# main_new_layout.net
KiCad netlist of a schematic drawn in EAGLE
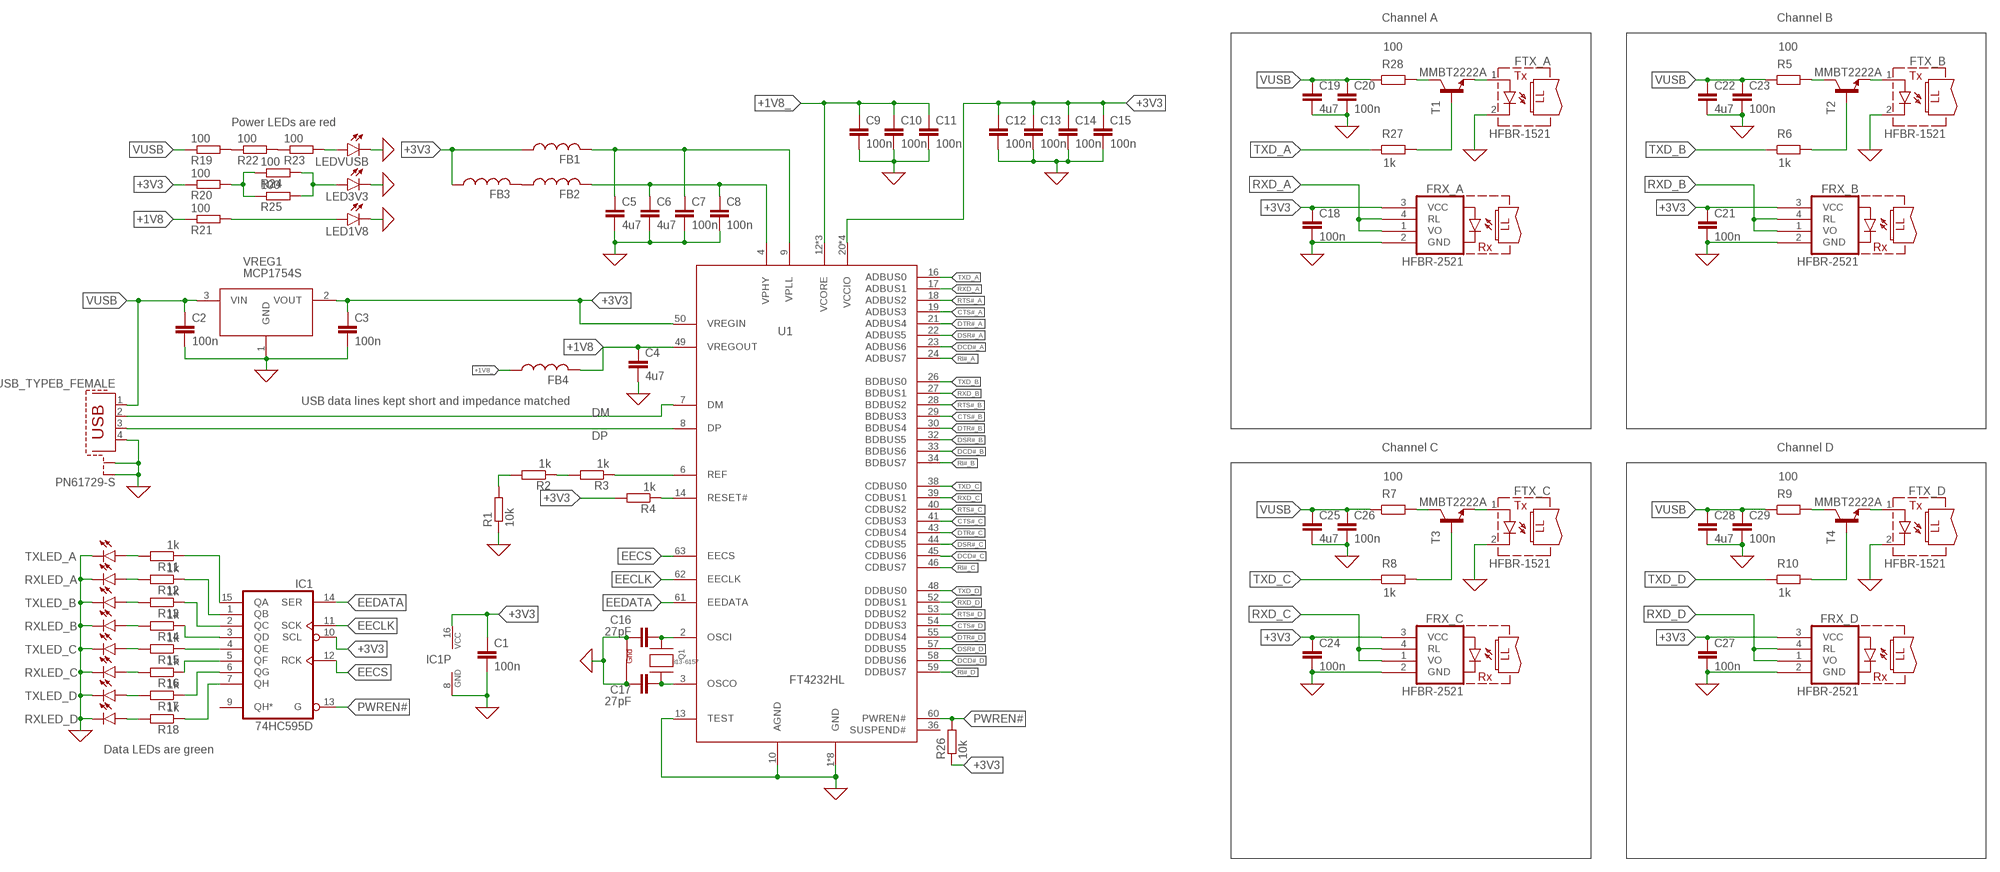
[diagram p0: schematic, sheet 1]

(export (version "E")
  (design (tool "Eeschema 10.0.6"))
  (components
    (comp (ref "C1")
      (value "100n")
      (footprint "eagle-import:C0805")
      (libsource (lib "eagle-import") (part "C-EUC0805"))
    )
    (comp (ref "C2")
      (value "100n")
      (footprint "eagle-import:C0805")
      (libsource (lib "eagle-import") (part "C-EUC0805"))
    )
    (comp (ref "C3")
      (value "100n")
      (footprint "eagle-import:C0805")
      (libsource (lib "eagle-import") (part "C-EUC0805"))
    )
    (comp (ref "C4")
      (value "4u7")
      (footprint "eagle-import:C0805")
      (libsource (lib "eagle-import") (part "C-EUC0805"))
    )
    (comp (ref "C5")
      (value "4u7")
      (footprint "eagle-import:C0805")
      (libsource (lib "eagle-import") (part "C-EUC0805"))
    )
    (comp (ref "C6")
      (value "4u7")
      (footprint "eagle-import:C0805")
      (libsource (lib "eagle-import") (part "C-EUC0805"))
    )
    (comp (ref "C7")
      (value "100n")
      (footprint "eagle-import:C0805")
      (libsource (lib "eagle-import") (part "C-EUC0805"))
    )
    (comp (ref "C8")
      (value "100n")
      (footprint "eagle-import:C0805")
      (libsource (lib "eagle-import") (part "C-EUC0805"))
    )
    (comp (ref "C9")
      (value "100n")
      (footprint "eagle-import:C0805")
      (libsource (lib "eagle-import") (part "C-EUC0805"))
    )
    (comp (ref "C10")
      (value "100n")
      (footprint "eagle-import:C0805")
      (libsource (lib "eagle-import") (part "C-EUC0805"))
    )
    (comp (ref "C11")
      (value "100n")
      (footprint "eagle-import:C0805")
      (libsource (lib "eagle-import") (part "C-EUC0805"))
    )
    (comp (ref "C12")
      (value "100n")
      (footprint "eagle-import:C0805")
      (libsource (lib "eagle-import") (part "C-EUC0805"))
    )
    (comp (ref "C13")
      (value "100n")
      (footprint "eagle-import:C0805")
      (libsource (lib "eagle-import") (part "C-EUC0805"))
    )
    (comp (ref "C14")
      (value "100n")
      (footprint "eagle-import:C0805")
      (libsource (lib "eagle-import") (part "C-EUC0805"))
    )
    (comp (ref "C15")
      (value "100n")
      (footprint "eagle-import:C0805")
      (libsource (lib "eagle-import") (part "C-EUC0805"))
    )
    (comp (ref "C16")
      (value "27pF")
      (footprint "eagle-import:C0805")
      (libsource (lib "eagle-import") (part "C-EUC0805"))
    )
    (comp (ref "C17")
      (value "27pF")
      (footprint "eagle-import:C0805")
      (libsource (lib "eagle-import") (part "C-EUC0805"))
    )
    (comp (ref "C18")
      (value "100n")
      (footprint "eagle-import:C0805")
      (libsource (lib "eagle-import") (part "C-EUC0805"))
    )
    (comp (ref "C19")
      (value "4u7")
      (footprint "eagle-import:C0805")
      (libsource (lib "eagle-import") (part "C-EUC0805"))
    )
    (comp (ref "C20")
      (value "100n")
      (footprint "eagle-import:C0805")
      (libsource (lib "eagle-import") (part "C-EUC0805"))
    )
    (comp (ref "C21")
      (value "100n")
      (footprint "eagle-import:C0805")
      (libsource (lib "eagle-import") (part "C-EUC0805"))
    )
    (comp (ref "C22")
      (value "4u7")
      (footprint "eagle-import:C0805")
      (libsource (lib "eagle-import") (part "C-EUC0805"))
    )
    (comp (ref "C23")
      (value "100n")
      (footprint "eagle-import:C0805")
      (libsource (lib "eagle-import") (part "C-EUC0805"))
    )
    (comp (ref "C24")
      (value "100n")
      (footprint "eagle-import:C0805")
      (libsource (lib "eagle-import") (part "C-EUC0805"))
    )
    (comp (ref "C25")
      (value "4u7")
      (footprint "eagle-import:C0805")
      (libsource (lib "eagle-import") (part "C-EUC0805"))
    )
    (comp (ref "C26")
      (value "100n")
      (footprint "eagle-import:C0805")
      (libsource (lib "eagle-import") (part "C-EUC0805"))
    )
    (comp (ref "C27")
      (value "100n")
      (footprint "eagle-import:C0805")
      (libsource (lib "eagle-import") (part "C-EUC0805"))
    )
    (comp (ref "C28")
      (value "4u7")
      (footprint "eagle-import:C0805")
      (libsource (lib "eagle-import") (part "C-EUC0805"))
    )
    (comp (ref "C29")
      (value "100n")
      (footprint "eagle-import:C0805")
      (libsource (lib "eagle-import") (part "C-EUC0805"))
    )
    (comp (ref "FB1")
      (value "FERRITE")
      (footprint "eagle-import:R0805")
      (libsource (lib "eagle-import") (part "FERRITE"))
    )
    (comp (ref "FB2")
      (value "FERRITE")
      (footprint "eagle-import:R0805")
      (libsource (lib "eagle-import") (part "FERRITE"))
    )
    (comp (ref "FB3")
      (value "FERRITE")
      (footprint "eagle-import:R0805")
      (libsource (lib "eagle-import") (part "FERRITE"))
    )
    (comp (ref "FB4")
      (value "FERRITE")
      (footprint "eagle-import:R0805")
      (libsource (lib "eagle-import") (part "FERRITE"))
    )
    (comp (ref "FRX_A")
      (value "HFBR-2521")
      (footprint "eagle-import:HFBR-15X3")
      (fields (field (name "MF") "AGILENT TECHNOLOGIES"))
      (libsource (lib "eagle-import") (part "HFBR-2521"))
    )
    (comp (ref "FRX_B")
      (value "HFBR-2521")
      (footprint "eagle-import:HFBR-15X3")
      (fields (field (name "MF") "AGILENT TECHNOLOGIES"))
      (libsource (lib "eagle-import") (part "HFBR-2521"))
    )
    (comp (ref "FRX_C")
      (value "HFBR-2521")
      (footprint "eagle-import:HFBR-15X3")
      (fields (field (name "MF") "AGILENT TECHNOLOGIES"))
      (libsource (lib "eagle-import") (part "HFBR-2521"))
    )
    (comp (ref "FRX_D")
      (value "HFBR-2521")
      (footprint "eagle-import:HFBR-15X3")
      (fields (field (name "MF") "AGILENT TECHNOLOGIES"))
      (libsource (lib "eagle-import") (part "HFBR-2521"))
    )
    (comp (ref "FTX_A")
      (value "HFBR-1521")
      (footprint "eagle-import:HFBR-15X3")
      (fields (field (name "MF") "AGILENT TECHNOLOGIES"))
      (libsource (lib "eagle-import") (part "HFBR-1521"))
    )
    (comp (ref "FTX_B")
      (value "HFBR-1521")
      (footprint "eagle-import:HFBR-15X3")
      (fields (field (name "MF") "AGILENT TECHNOLOGIES"))
      (libsource (lib "eagle-import") (part "HFBR-1521"))
    )
    (comp (ref "FTX_C")
      (value "HFBR-1521")
      (footprint "eagle-import:HFBR-15X3")
      (fields (field (name "MF") "AGILENT TECHNOLOGIES"))
      (libsource (lib "eagle-import") (part "HFBR-1521"))
    )
    (comp (ref "FTX_D")
      (value "HFBR-1521")
      (footprint "eagle-import:HFBR-15X3")
      (fields (field (name "MF") "AGILENT TECHNOLOGIES"))
      (libsource (lib "eagle-import") (part "HFBR-1521"))
    )
    (comp (ref "IC1")
      (value "74HC595D")
      (footprint "eagle-import:SO16")
      (libsource (lib "eagle-import") (part "74595DHC"))
    )
    (comp (ref "LED1V8")
      (value "LEDCHIP-LED0805")
      (footprint "eagle-import:CHIP-LED0805")
      (libsource (lib "eagle-import") (part "LEDCHIP-LED0805"))
    )
    (comp (ref "LED3V3")
      (value "LEDCHIP-LED0805")
      (footprint "eagle-import:CHIP-LED0805")
      (libsource (lib "eagle-import") (part "LEDCHIP-LED0805"))
    )
    (comp (ref "LEDVUSB")
      (value "LEDCHIP-LED0805")
      (footprint "eagle-import:CHIP-LED0805")
      (libsource (lib "eagle-import") (part "LEDCHIP-LED0805"))
    )
    (comp (ref "Q1")
      (value "XTAL-4-3225")
      (footprint "eagle-import:NX3225")
      (libsource (lib "eagle-import") (part "XTAL-4-3225"))
    )
    (comp (ref "R1")
      (value "10k")
      (footprint "eagle-import:R0805")
      (libsource (lib "eagle-import") (part "R-EU_R0805"))
    )
    (comp (ref "R2")
      (value "1k")
      (footprint "eagle-import:R0805")
      (libsource (lib "eagle-import") (part "R-EU_R0805"))
    )
    (comp (ref "R3")
      (value "1k")
      (footprint "eagle-import:R0805")
      (libsource (lib "eagle-import") (part "R-EU_R0805"))
    )
    (comp (ref "R4")
      (value "1k")
      (footprint "eagle-import:R0805")
      (libsource (lib "eagle-import") (part "R-EU_R0805"))
    )
    (comp (ref "R5")
      (value "100")
      (footprint "eagle-import:R0805")
      (fields (field (name "SPICEPREFIX") "R"))
      (libsource (lib "eagle-import") (part "R-EU_R0805"))
    )
    (comp (ref "R6")
      (value "1k")
      (footprint "eagle-import:R0805")
      (libsource (lib "eagle-import") (part "R-EU_R0805"))
    )
    (comp (ref "R7")
      (value "100")
      (footprint "eagle-import:R0805")
      (fields (field (name "SPICEPREFIX") "R"))
      (libsource (lib "eagle-import") (part "R-EU_R0805"))
    )
    (comp (ref "R8")
      (value "1k")
      (footprint "eagle-import:R0805")
      (libsource (lib "eagle-import") (part "R-EU_R0805"))
    )
    (comp (ref "R9")
      (value "100")
      (footprint "eagle-import:R0805")
      (fields (field (name "SPICEPREFIX") "R"))
      (libsource (lib "eagle-import") (part "R-EU_R0805"))
    )
    (comp (ref "R10")
      (value "1k")
      (footprint "eagle-import:R0805")
      (libsource (lib "eagle-import") (part "R-EU_R0805"))
    )
    (comp (ref "R11")
      (value "1k")
      (footprint "eagle-import:R0805")
      (libsource (lib "eagle-import") (part "R-EU_R0805"))
    )
    (comp (ref "R12")
      (value "1k")
      (footprint "eagle-import:R0805")
      (libsource (lib "eagle-import") (part "R-EU_R0805"))
    )
    (comp (ref "R13")
      (value "1k")
      (footprint "eagle-import:R0805")
      (libsource (lib "eagle-import") (part "R-EU_R0805"))
    )
    (comp (ref "R14")
      (value "1k")
      (footprint "eagle-import:R0805")
      (libsource (lib "eagle-import") (part "R-EU_R0805"))
    )
    (comp (ref "R15")
      (value "1k")
      (footprint "eagle-import:R0805")
      (libsource (lib "eagle-import") (part "R-EU_R0805"))
    )
    (comp (ref "R16")
      (value "1k")
      (footprint "eagle-import:R0805")
      (libsource (lib "eagle-import") (part "R-EU_R0805"))
    )
    (comp (ref "R17")
      (value "1k")
      (footprint "eagle-import:R0805")
      (libsource (lib "eagle-import") (part "R-EU_R0805"))
    )
    (comp (ref "R18")
      (value "1k")
      (footprint "eagle-import:R0805")
      (libsource (lib "eagle-import") (part "R-EU_R0805"))
    )
    (comp (ref "R19")
      (value "100")
      (footprint "eagle-import:R0805")
      (libsource (lib "eagle-import") (part "R-EU_R0805"))
    )
    (comp (ref "R20")
      (value "100")
      (footprint "eagle-import:R0805")
      (libsource (lib "eagle-import") (part "R-EU_R0805"))
    )
    (comp (ref "R21")
      (value "100")
      (footprint "eagle-import:R0805")
      (libsource (lib "eagle-import") (part "R-EU_R0805"))
    )
    (comp (ref "R22")
      (value "100")
      (footprint "eagle-import:R0805")
      (libsource (lib "eagle-import") (part "R-EU_R0805"))
    )
    (comp (ref "R23")
      (value "100")
      (footprint "eagle-import:R0805")
      (libsource (lib "eagle-import") (part "R-EU_R0805"))
    )
    (comp (ref "R24")
      (value "100")
      (footprint "eagle-import:R0805")
      (libsource (lib "eagle-import") (part "R-EU_R0805"))
    )
    (comp (ref "R25")
      (value "100")
      (footprint "eagle-import:R0805")
      (libsource (lib "eagle-import") (part "R-EU_R0805"))
    )
    (comp (ref "R26")
      (value "10k")
      (footprint "eagle-import:R0805")
      (libsource (lib "eagle-import") (part "R-EU_R0805"))
    )
    (comp (ref "R27")
      (value "1k")
      (footprint "eagle-import:R0805")
      (libsource (lib "eagle-import") (part "R-EU_R0805"))
    )
    (comp (ref "R28")
      (value "100")
      (footprint "eagle-import:R0805")
      (fields (field (name "SPICEPREFIX") "R"))
      (libsource (lib "eagle-import") (part "R-EU_R0805"))
    )
    (comp (ref "RXLED_A")
      (value "LEDCHIP-LED0805")
      (footprint "eagle-import:CHIP-LED0805")
      (libsource (lib "eagle-import") (part "LEDCHIP-LED0805"))
    )
    (comp (ref "RXLED_B")
      (value "LEDCHIP-LED0805")
      (footprint "eagle-import:CHIP-LED0805")
      (libsource (lib "eagle-import") (part "LEDCHIP-LED0805"))
    )
    (comp (ref "RXLED_C")
      (value "LEDCHIP-LED0805")
      (footprint "eagle-import:CHIP-LED0805")
      (libsource (lib "eagle-import") (part "LEDCHIP-LED0805"))
    )
    (comp (ref "RXLED_D")
      (value "LEDCHIP-LED0805")
      (footprint "eagle-import:CHIP-LED0805")
      (libsource (lib "eagle-import") (part "LEDCHIP-LED0805"))
    )
    (comp (ref "T1")
      (value "MMBT2222A")
      (footprint "eagle-import:SOT23-BEC")
      (libsource (lib "eagle-import") (part "-NPN-SOT23-BECBC847A"))
    )
    (comp (ref "T2")
      (value "MMBT2222A")
      (footprint "eagle-import:SOT23-BEC")
      (libsource (lib "eagle-import") (part "-NPN-SOT23-BECBC847A"))
    )
    (comp (ref "T3")
      (value "MMBT2222A")
      (footprint "eagle-import:SOT23-BEC")
      (libsource (lib "eagle-import") (part "-NPN-SOT23-BECBC847A"))
    )
    (comp (ref "T4")
      (value "MMBT2222A")
      (footprint "eagle-import:SOT23-BEC")
      (libsource (lib "eagle-import") (part "-NPN-SOT23-BECBC847A"))
    )
    (comp (ref "TXLED_A")
      (value "LEDCHIP-LED0805")
      (footprint "eagle-import:CHIP-LED0805")
      (libsource (lib "eagle-import") (part "LEDCHIP-LED0805"))
    )
    (comp (ref "TXLED_B")
      (value "LEDCHIP-LED0805")
      (footprint "eagle-import:CHIP-LED0805")
      (libsource (lib "eagle-import") (part "LEDCHIP-LED0805"))
    )
    (comp (ref "TXLED_C")
      (value "LEDCHIP-LED0805")
      (footprint "eagle-import:CHIP-LED0805")
      (libsource (lib "eagle-import") (part "LEDCHIP-LED0805"))
    )
    (comp (ref "TXLED_D")
      (value "LEDCHIP-LED0805")
      (footprint "eagle-import:CHIP-LED0805")
      (libsource (lib "eagle-import") (part "LEDCHIP-LED0805"))
    )
    (comp (ref "U1")
      (value "FT4232HL")
      (footprint "eagle-import:LQFP-ST-64-2")
      (libsource (lib "eagle-import") (part "FT4232HL"))
    )
    (comp (ref "USB_TYPEB_FEMALE")
      (value "PN61729-S")
      (footprint "eagle-import:PN61729-S")
      (libsource (lib "eagle-import") (part "PN61729-S"))
    )
    (comp (ref "VREG1")
      (value "MCP1754S")
      (footprint "eagle-import:SOT23")
      (libsource (lib "eagle-import") (part "MCP1754S"))
    )
  )
  (nets
    (net (code "1") (name "+1V8") (class "Default")
      (node (ref "C4") (pin "1") (pinfunction "1_1") (pintype "passive"))
      (node (ref "FB4") (pin "2") (pinfunction "2_2") (pintype "passive"))
      (node (ref "R21") (pin "1") (pinfunction "1_1") (pintype "passive"))
      (node (ref "U1") (pin "49") (pinfunction "VREGOUT_49") (pintype "bidirectional"))
    )
    (net (code "2") (name "+1V8_") (class "Default")
      (node (ref "C10") (pin "1") (pinfunction "1_1") (pintype "passive"))
      (node (ref "C11") (pin "1") (pinfunction "1_1") (pintype "passive"))
      (node (ref "C9") (pin "1") (pinfunction "1_1") (pintype "passive"))
      (node (ref "FB4") (pin "1") (pinfunction "1_1") (pintype "passive"))
      (node (ref "U1") (pin "12") (pinfunction "VCORE_12") (pintype "bidirectional"))
      (node (ref "U1") (pin "37") (pinfunction "VCORE_37") (pintype "bidirectional"))
      (node (ref "U1") (pin "64") (pinfunction "VCORE_64") (pintype "bidirectional"))
    )
    (net (code "3") (name "+3V3") (class "Default")
      (node (ref "C1") (pin "1") (pinfunction "1_1") (pintype "passive"))
      (node (ref "C12") (pin "1") (pinfunction "1_1") (pintype "passive"))
      (node (ref "C13") (pin "1") (pinfunction "1_1") (pintype "passive"))
      (node (ref "C14") (pin "1") (pinfunction "1_1") (pintype "passive"))
      (node (ref "C15") (pin "1") (pinfunction "1_1") (pintype "passive"))
      (node (ref "C18") (pin "1") (pinfunction "1_1") (pintype "passive"))
      (node (ref "C21") (pin "1") (pinfunction "1_1") (pintype "passive"))
      (node (ref "C24") (pin "1") (pinfunction "1_1") (pintype "passive"))
      (node (ref "C27") (pin "1") (pinfunction "1_1") (pintype "passive"))
      (node (ref "C3") (pin "1") (pinfunction "1_1") (pintype "passive"))
      (node (ref "FB1") (pin "1") (pinfunction "1_1") (pintype "passive"))
      (node (ref "FB3") (pin "1") (pinfunction "1_1") (pintype "passive"))
      (node (ref "FRX_A") (pin "3") (pinfunction "VCC_3") (pintype "power_in"))
      (node (ref "FRX_B") (pin "3") (pinfunction "VCC_3") (pintype "power_in"))
      (node (ref "FRX_C") (pin "3") (pinfunction "VCC_3") (pintype "power_in"))
      (node (ref "FRX_D") (pin "3") (pinfunction "VCC_3") (pintype "power_in"))
      (node (ref "IC1") (pin "10") (pinfunction "SCL_10") (pintype "input"))
      (node (ref "IC1") (pin "16") (pinfunction "VCC_16") (pintype "power_in"))
      (node (ref "R20") (pin "1") (pinfunction "1_1") (pintype "passive"))
      (node (ref "R26") (pin "1") (pinfunction "1_1") (pintype "passive"))
      (node (ref "R4") (pin "2") (pinfunction "2_2") (pintype "passive"))
      (node (ref "U1") (pin "20") (pinfunction "VCCIO_20") (pintype "bidirectional"))
      (node (ref "U1") (pin "31") (pinfunction "VCCIO_31") (pintype "bidirectional"))
      (node (ref "U1") (pin "42") (pinfunction "VCCIO_42") (pintype "bidirectional"))
      (node (ref "U1") (pin "50") (pinfunction "VREGIN_50") (pintype "bidirectional"))
      (node (ref "U1") (pin "56") (pinfunction "VCCIO_56") (pintype "bidirectional"))
      (node (ref "VREG1") (pin "2") (pinfunction "VOUT_2") (pintype "bidirectional"))
    )
    (net (code "4") (name "/DM") (class "Default")
      (node (ref "U1") (pin "7") (pinfunction "DM_7") (pintype "bidirectional"))
      (node (ref "USB_TYPEB_FEMALE") (pin "2") (pinfunction "2_2") (pintype "passive"))
    )
    (net (code "5") (name "/DP") (class "Default")
      (node (ref "U1") (pin "8") (pinfunction "DP_8") (pintype "bidirectional"))
      (node (ref "USB_TYPEB_FEMALE") (pin "3") (pinfunction "3_3") (pintype "passive"))
    )
    (net (code "6") (name "CTS#_A") (class "Default")
      (node (ref "U1") (pin "19") (pinfunction "ADBUS3_19") (pintype "bidirectional"))
    )
    (net (code "7") (name "CTS#_B") (class "Default")
      (node (ref "U1") (pin "29") (pinfunction "BDBUS3_29") (pintype "bidirectional"))
    )
    (net (code "8") (name "CTS#_C") (class "Default")
      (node (ref "U1") (pin "41") (pinfunction "CDBUS3_41") (pintype "bidirectional"))
    )
    (net (code "9") (name "CTS#_D") (class "Default")
      (node (ref "U1") (pin "54") (pinfunction "DDBUS3_54") (pintype "bidirectional"))
    )
    (net (code "10") (name "DCD#_A") (class "Default")
      (node (ref "U1") (pin "23") (pinfunction "ADBUS6_23") (pintype "bidirectional"))
    )
    (net (code "11") (name "DCD#_B") (class "Default")
      (node (ref "U1") (pin "33") (pinfunction "BDBUS6_33") (pintype "bidirectional"))
    )
    (net (code "12") (name "DCD#_C") (class "Default")
      (node (ref "U1") (pin "45") (pinfunction "CDBUS6_45") (pintype "bidirectional"))
    )
    (net (code "13") (name "DCD#_D") (class "Default")
      (node (ref "U1") (pin "58") (pinfunction "DDBUS6_58") (pintype "bidirectional"))
    )
    (net (code "14") (name "DSR#_A") (class "Default")
      (node (ref "U1") (pin "22") (pinfunction "ADBUS5_22") (pintype "bidirectional"))
    )
    (net (code "15") (name "DSR#_B") (class "Default")
      (node (ref "U1") (pin "32") (pinfunction "BDBUS5_32") (pintype "bidirectional"))
    )
    (net (code "16") (name "DSR#_C") (class "Default")
      (node (ref "U1") (pin "44") (pinfunction "CDBUS5_44") (pintype "bidirectional"))
    )
    (net (code "17") (name "DSR#_D") (class "Default")
      (node (ref "U1") (pin "57") (pinfunction "DDBUS5_57") (pintype "bidirectional"))
    )
    (net (code "18") (name "DTR#_A") (class "Default")
      (node (ref "U1") (pin "21") (pinfunction "ADBUS4_21") (pintype "bidirectional"))
    )
    (net (code "19") (name "DTR#_B") (class "Default")
      (node (ref "U1") (pin "30") (pinfunction "BDBUS4_30") (pintype "bidirectional"))
    )
    (net (code "20") (name "DTR#_C") (class "Default")
      (node (ref "U1") (pin "43") (pinfunction "CDBUS4_43") (pintype "bidirectional"))
    )
    (net (code "21") (name "DTR#_D") (class "Default")
      (node (ref "U1") (pin "55") (pinfunction "DDBUS4_55") (pintype "bidirectional"))
    )
    (net (code "22") (name "EECLK") (class "Default")
      (node (ref "IC1") (pin "11") (pinfunction "SCK_11") (pintype "input"))
      (node (ref "U1") (pin "62") (pinfunction "EECLK_62") (pintype "bidirectional"))
    )
    (net (code "23") (name "EECS") (class "Default")
      (node (ref "IC1") (pin "12") (pinfunction "RCK_12") (pintype "input"))
      (node (ref "U1") (pin "63") (pinfunction "EECS_63") (pintype "bidirectional"))
    )
    (net (code "24") (name "EEDATA") (class "Default")
      (node (ref "IC1") (pin "14") (pinfunction "SER_14") (pintype "input"))
      (node (ref "U1") (pin "61") (pinfunction "EEDATA_61") (pintype "bidirectional"))
    )
    (net (code "25") (name "GND") (class "Default")
      (node (ref "C1") (pin "2") (pinfunction "2_2") (pintype "passive"))
      (node (ref "C10") (pin "2") (pinfunction "2_2") (pintype "passive"))
      (node (ref "C11") (pin "2") (pinfunction "2_2") (pintype "passive"))
      (node (ref "C12") (pin "2") (pinfunction "2_2") (pintype "passive"))
      (node (ref "C13") (pin "2") (pinfunction "2_2") (pintype "passive"))
      (node (ref "C14") (pin "2") (pinfunction "2_2") (pintype "passive"))
      (node (ref "C15") (pin "2") (pinfunction "2_2") (pintype "passive"))
      (node (ref "C16") (pin "2") (pinfunction "2_2") (pintype "passive"))
      (node (ref "C17") (pin "2") (pinfunction "2_2") (pintype "passive"))
      (node (ref "C18") (pin "2") (pinfunction "2_2") (pintype "passive"))
      (node (ref "C19") (pin "2") (pinfunction "2_2") (pintype "passive"))
      (node (ref "C2") (pin "2") (pinfunction "2_2") (pintype "passive"))
      (node (ref "C20") (pin "2") (pinfunction "2_2") (pintype "passive"))
      (node (ref "C21") (pin "2") (pinfunction "2_2") (pintype "passive"))
      (node (ref "C22") (pin "2") (pinfunction "2_2") (pintype "passive"))
      (node (ref "C23") (pin "2") (pinfunction "2_2") (pintype "passive"))
      (node (ref "C24") (pin "2") (pinfunction "2_2") (pintype "passive"))
      (node (ref "C25") (pin "2") (pinfunction "2_2") (pintype "passive"))
      (node (ref "C26") (pin "2") (pinfunction "2_2") (pintype "passive"))
      (node (ref "C27") (pin "2") (pinfunction "2_2") (pintype "passive"))
      (node (ref "C28") (pin "2") (pinfunction "2_2") (pintype "passive"))
      (node (ref "C29") (pin "2") (pinfunction "2_2") (pintype "passive"))
      (node (ref "C3") (pin "2") (pinfunction "2_2") (pintype "passive"))
      (node (ref "C4") (pin "2") (pinfunction "2_2") (pintype "passive"))
      (node (ref "C5") (pin "2") (pinfunction "2_2") (pintype "passive"))
      (node (ref "C6") (pin "2") (pinfunction "2_2") (pintype "passive"))
      (node (ref "C7") (pin "2") (pinfunction "2_2") (pintype "passive"))
      (node (ref "C8") (pin "2") (pinfunction "2_2") (pintype "passive"))
      (node (ref "C9") (pin "2") (pinfunction "2_2") (pintype "passive"))
      (node (ref "FRX_A") (pin "2") (pinfunction "GND_2") (pintype "power_in"))
      (node (ref "FRX_B") (pin "2") (pinfunction "GND_2") (pintype "power_in"))
      (node (ref "FRX_C") (pin "2") (pinfunction "GND_2") (pintype "power_in"))
      (node (ref "FRX_D") (pin "2") (pinfunction "GND_2") (pintype "power_in"))
      (node (ref "FTX_A") (pin "2") (pinfunction "C_2") (pintype "passive"))
      (node (ref "FTX_B") (pin "2") (pinfunction "C_2") (pintype "passive"))
      (node (ref "FTX_C") (pin "2") (pinfunction "C_2") (pintype "passive"))
      (node (ref "FTX_D") (pin "2") (pinfunction "C_2") (pintype "passive"))
      (node (ref "IC1") (pin "8") (pinfunction "GND_8") (pintype "power_in"))
      (node (ref "LED1V8") (pin "C") (pinfunction "C_C") (pintype "passive"))
      (node (ref "LED3V3") (pin "C") (pinfunction "C_C") (pintype "passive"))
      (node (ref "LEDVUSB") (pin "C") (pinfunction "C_C") (pintype "passive"))
      (node (ref "Q1") (pin "2") (pinfunction "G2_2") (pintype "power_in"))
      (node (ref "Q1") (pin "4") (pinfunction "G1_4") (pintype "power_in"))
      (node (ref "R1") (pin "1") (pinfunction "1_1") (pintype "passive"))
      (node (ref "RXLED_A") (pin "C") (pinfunction "C_C") (pintype "passive"))
      (node (ref "RXLED_B") (pin "C") (pinfunction "C_C") (pintype "passive"))
      (node (ref "RXLED_C") (pin "C") (pinfunction "C_C") (pintype "passive"))
      (node (ref "RXLED_D") (pin "C") (pinfunction "C_C") (pintype "passive"))
      (node (ref "TXLED_A") (pin "C") (pinfunction "C_C") (pintype "passive"))
      (node (ref "TXLED_B") (pin "C") (pinfunction "C_C") (pintype "passive"))
      (node (ref "TXLED_C") (pin "C") (pinfunction "C_C") (pintype "passive"))
      (node (ref "TXLED_D") (pin "C") (pinfunction "C_C") (pintype "passive"))
      (node (ref "U1") (pin "1") (pinfunction "GND_1") (pintype "bidirectional"))
      (node (ref "U1") (pin "10") (pinfunction "AGND_10") (pintype "bidirectional"))
      (node (ref "U1") (pin "11") (pinfunction "GND_11") (pintype "bidirectional"))
      (node (ref "U1") (pin "13") (pinfunction "TEST_13") (pintype "bidirectional"))
      (node (ref "U1") (pin "15") (pinfunction "GND_15") (pintype "bidirectional"))
      (node (ref "U1") (pin "25") (pinfunction "GND_25") (pintype "bidirectional"))
      (node (ref "U1") (pin "35") (pinfunction "GND_35") (pintype "bidirectional"))
      (node (ref "U1") (pin "47") (pinfunction "GND_47") (pintype "bidirectional"))
      (node (ref "U1") (pin "5") (pinfunction "GND_5") (pintype "bidirectional"))
      (node (ref "U1") (pin "51") (pinfunction "GND_51") (pintype "bidirectional"))
      (node (ref "USB_TYPEB_FEMALE") (pin "4") (pinfunction "4_4") (pintype "passive"))
      (node (ref "USB_TYPEB_FEMALE") (pin "S1") (pinfunction "S1_S1") (pintype "passive"))
      (node (ref "USB_TYPEB_FEMALE") (pin "S2") (pinfunction "S2_S2") (pintype "passive"))
      (node (ref "VREG1") (pin "1") (pinfunction "GND_1") (pintype "bidirectional"))
    )
    (net (code "26") (name "Net-(FB2-Pad1)") (class "Default")
      (node (ref "FB2") (pin "1") (pinfunction "1_1") (pintype "passive"))
      (node (ref "FB3") (pin "2") (pinfunction "2_2") (pintype "passive"))
    )
    (net (code "27") (name "Net-(FTX_A-A)") (class "Default")
      (node (ref "FTX_A") (pin "1") (pinfunction "A_1") (pintype "passive"))
      (node (ref "T1") (pin "E") (pinfunction "E_E") (pintype "passive"))
    )
    (net (code "28") (name "Net-(FTX_B-A)") (class "Default")
      (node (ref "FTX_B") (pin "1") (pinfunction "A_1") (pintype "passive"))
      (node (ref "T2") (pin "E") (pinfunction "E_E") (pintype "passive"))
    )
    (net (code "29") (name "Net-(FTX_C-A)") (class "Default")
      (node (ref "FTX_C") (pin "1") (pinfunction "A_1") (pintype "passive"))
      (node (ref "T3") (pin "E") (pinfunction "E_E") (pintype "passive"))
    )
    (net (code "30") (name "Net-(FTX_D-A)") (class "Default")
      (node (ref "FTX_D") (pin "1") (pinfunction "A_1") (pintype "passive"))
      (node (ref "T4") (pin "E") (pinfunction "E_E") (pintype "passive"))
    )
    (net (code "31") (name "Net-(IC1A-QA)") (class "Default")
      (node (ref "IC1") (pin "15") (pinfunction "QA_15") (pintype "tri_state"))
      (node (ref "R11") (pin "1") (pinfunction "1_1") (pintype "passive"))
    )
    (net (code "32") (name "Net-(IC1A-QB)") (class "Default")
      (node (ref "IC1") (pin "1") (pinfunction "QB_1") (pintype "tri_state"))
      (node (ref "R12") (pin "1") (pinfunction "1_1") (pintype "passive"))
    )
    (net (code "33") (name "Net-(IC1A-QC)") (class "Default")
      (node (ref "IC1") (pin "2") (pinfunction "QC_2") (pintype "tri_state"))
      (node (ref "R13") (pin "1") (pinfunction "1_1") (pintype "passive"))
    )
    (net (code "34") (name "Net-(IC1A-QD)") (class "Default")
      (node (ref "IC1") (pin "3") (pinfunction "QD_3") (pintype "tri_state"))
      (node (ref "R14") (pin "1") (pinfunction "1_1") (pintype "passive"))
    )
    (net (code "35") (name "Net-(IC1A-QE)") (class "Default")
      (node (ref "IC1") (pin "4") (pinfunction "QE_4") (pintype "tri_state"))
      (node (ref "R15") (pin "1") (pinfunction "1_1") (pintype "passive"))
    )
    (net (code "36") (name "Net-(IC1A-QF)") (class "Default")
      (node (ref "IC1") (pin "5") (pinfunction "QF_5") (pintype "tri_state"))
      (node (ref "R16") (pin "1") (pinfunction "1_1") (pintype "passive"))
    )
    (net (code "37") (name "Net-(IC1A-QG)") (class "Default")
      (node (ref "IC1") (pin "6") (pinfunction "QG_6") (pintype "tri_state"))
      (node (ref "R17") (pin "1") (pinfunction "1_1") (pintype "passive"))
    )
    (net (code "38") (name "Net-(IC1A-QH)") (class "Default")
      (node (ref "IC1") (pin "7") (pinfunction "QH_7") (pintype "tri_state"))
      (node (ref "R18") (pin "1") (pinfunction "1_1") (pintype "passive"))
    )
    (net (code "39") (name "Net-(LED1V8-PadA)") (class "Default")
      (node (ref "LED1V8") (pin "A") (pinfunction "A_A") (pintype "passive"))
      (node (ref "R21") (pin "2") (pinfunction "2_2") (pintype "passive"))
    )
    (net (code "40") (name "Net-(LED3V3-PadA)") (class "Default")
      (node (ref "LED3V3") (pin "A") (pinfunction "A_A") (pintype "passive"))
      (node (ref "R24") (pin "2") (pinfunction "2_2") (pintype "passive"))
      (node (ref "R25") (pin "2") (pinfunction "2_2") (pintype "passive"))
    )
    (net (code "41") (name "Net-(LEDVUSB-PadA)") (class "Default")
      (node (ref "LEDVUSB") (pin "A") (pinfunction "A_A") (pintype "passive"))
      (node (ref "R23") (pin "2") (pinfunction "2_2") (pintype "passive"))
    )
    (net (code "42") (name "Net-(Q1-X1)") (class "Default")
      (node (ref "C16") (pin "1") (pinfunction "1_1") (pintype "passive"))
      (node (ref "Q1") (pin "1") (pinfunction "X1_1") (pintype "bidirectional"))
      (node (ref "U1") (pin "2") (pinfunction "OSCI_2") (pintype "bidirectional"))
    )
    (net (code "43") (name "Net-(Q1-X2)") (class "Default")
      (node (ref "C17") (pin "1") (pinfunction "1_1") (pintype "passive"))
      (node (ref "Q1") (pin "3") (pinfunction "X2_3") (pintype "bidirectional"))
      (node (ref "U1") (pin "3") (pinfunction "OSCO_3") (pintype "bidirectional"))
    )
    (net (code "44") (name "Net-(R1-Pad2)") (class "Default")
      (node (ref "R1") (pin "2") (pinfunction "2_2") (pintype "passive"))
      (node (ref "R2") (pin "2") (pinfunction "2_2") (pintype "passive"))
    )
    (net (code "45") (name "Net-(R2-Pad1)") (class "Default")
      (node (ref "R2") (pin "1") (pinfunction "1_1") (pintype "passive"))
      (node (ref "R3") (pin "2") (pinfunction "2_2") (pintype "passive"))
    )
    (net (code "46") (name "Net-(R5-Pad2)") (class "Default")
      (node (ref "R5") (pin "2") (pinfunction "2_2") (pintype "passive"))
      (node (ref "T2") (pin "C") (pinfunction "C_C") (pintype "passive"))
    )
    (net (code "47") (name "Net-(R6-Pad2)") (class "Default")
      (node (ref "R6") (pin "2") (pinfunction "2_2") (pintype "passive"))
      (node (ref "T2") (pin "B") (pinfunction "B_B") (pintype "passive"))
    )
    (net (code "48") (name "Net-(R7-Pad2)") (class "Default")
      (node (ref "R7") (pin "2") (pinfunction "2_2") (pintype "passive"))
      (node (ref "T3") (pin "C") (pinfunction "C_C") (pintype "passive"))
    )
    (net (code "49") (name "Net-(R8-Pad2)") (class "Default")
      (node (ref "R8") (pin "2") (pinfunction "2_2") (pintype "passive"))
      (node (ref "T3") (pin "B") (pinfunction "B_B") (pintype "passive"))
    )
    (net (code "50") (name "Net-(R9-Pad2)") (class "Default")
      (node (ref "R9") (pin "2") (pinfunction "2_2") (pintype "passive"))
      (node (ref "T4") (pin "C") (pinfunction "C_C") (pintype "passive"))
    )
    (net (code "51") (name "Net-(R10-Pad2)") (class "Default")
      (node (ref "R10") (pin "2") (pinfunction "2_2") (pintype "passive"))
      (node (ref "T4") (pin "B") (pinfunction "B_B") (pintype "passive"))
    )
    (net (code "52") (name "Net-(R11-Pad2)") (class "Default")
      (node (ref "R11") (pin "2") (pinfunction "2_2") (pintype "passive"))
      (node (ref "TXLED_A") (pin "A") (pinfunction "A_A") (pintype "passive"))
    )
    (net (code "53") (name "Net-(R12-Pad2)") (class "Default")
      (node (ref "R12") (pin "2") (pinfunction "2_2") (pintype "passive"))
      (node (ref "RXLED_A") (pin "A") (pinfunction "A_A") (pintype "passive"))
    )
    (net (code "54") (name "Net-(R13-Pad2)") (class "Default")
      (node (ref "R13") (pin "2") (pinfunction "2_2") (pintype "passive"))
      (node (ref "TXLED_B") (pin "A") (pinfunction "A_A") (pintype "passive"))
    )
    (net (code "55") (name "Net-(R14-Pad2)") (class "Default")
      (node (ref "R14") (pin "2") (pinfunction "2_2") (pintype "passive"))
      (node (ref "RXLED_B") (pin "A") (pinfunction "A_A") (pintype "passive"))
    )
    (net (code "56") (name "Net-(R15-Pad2)") (class "Default")
      (node (ref "R15") (pin "2") (pinfunction "2_2") (pintype "passive"))
      (node (ref "TXLED_C") (pin "A") (pinfunction "A_A") (pintype "passive"))
    )
    (net (code "57") (name "Net-(R16-Pad2)") (class "Default")
      (node (ref "R16") (pin "2") (pinfunction "2_2") (pintype "passive"))
      (node (ref "RXLED_C") (pin "A") (pinfunction "A_A") (pintype "passive"))
    )
    (net (code "58") (name "Net-(R17-Pad2)") (class "Default")
      (node (ref "R17") (pin "2") (pinfunction "2_2") (pintype "passive"))
      (node (ref "TXLED_D") (pin "A") (pinfunction "A_A") (pintype "passive"))
    )
    (net (code "59") (name "Net-(R18-Pad2)") (class "Default")
      (node (ref "R18") (pin "2") (pinfunction "2_2") (pintype "passive"))
      (node (ref "RXLED_D") (pin "A") (pinfunction "A_A") (pintype "passive"))
    )
    (net (code "60") (name "Net-(R19-Pad2)") (class "Default")
      (node (ref "R19") (pin "2") (pinfunction "2_2") (pintype "passive"))
      (node (ref "R22") (pin "1") (pinfunction "1_1") (pintype "passive"))
    )
    (net (code "61") (name "Net-(R20-Pad2)") (class "Default")
      (node (ref "R20") (pin "2") (pinfunction "2_2") (pintype "passive"))
      (node (ref "R24") (pin "1") (pinfunction "1_1") (pintype "passive"))
      (node (ref "R25") (pin "1") (pinfunction "1_1") (pintype "passive"))
    )
    (net (code "62") (name "Net-(R22-Pad2)") (class "Default")
      (node (ref "R22") (pin "2") (pinfunction "2_2") (pintype "passive"))
      (node (ref "R23") (pin "1") (pinfunction "1_1") (pintype "passive"))
    )
    (net (code "63") (name "Net-(R27-Pad2)") (class "Default")
      (node (ref "R27") (pin "2") (pinfunction "2_2") (pintype "passive"))
      (node (ref "T1") (pin "B") (pinfunction "B_B") (pintype "passive"))
    )
    (net (code "64") (name "Net-(R28-Pad2)") (class "Default")
      (node (ref "R28") (pin "2") (pinfunction "2_2") (pintype "passive"))
      (node (ref "T1") (pin "C") (pinfunction "C_C") (pintype "passive"))
    )
    (net (code "65") (name "Net-(U1-REF)") (class "Default")
      (node (ref "R3") (pin "1") (pinfunction "1_1") (pintype "passive"))
      (node (ref "U1") (pin "6") (pinfunction "REF_6") (pintype "bidirectional"))
    )
    (net (code "66") (name "Net-(U1-RESET#)") (class "Default")
      (node (ref "R4") (pin "1") (pinfunction "1_1") (pintype "passive"))
      (node (ref "U1") (pin "14") (pinfunction "RESET#_14") (pintype "bidirectional"))
    )
    (net (code "67") (name "Net-(U1-VPHY)") (class "Default")
      (node (ref "C6") (pin "1") (pinfunction "1_1") (pintype "passive"))
      (node (ref "C8") (pin "1") (pinfunction "1_1") (pintype "passive"))
      (node (ref "FB2") (pin "2") (pinfunction "2_2") (pintype "passive"))
      (node (ref "U1") (pin "4") (pinfunction "VPHY_4") (pintype "bidirectional"))
    )
    (net (code "68") (name "Net-(U1-VPLL)") (class "Default")
      (node (ref "C5") (pin "1") (pinfunction "1_1") (pintype "passive"))
      (node (ref "C7") (pin "1") (pinfunction "1_1") (pintype "passive"))
      (node (ref "FB1") (pin "2") (pinfunction "2_2") (pintype "passive"))
      (node (ref "U1") (pin "9") (pinfunction "VPLL_9") (pintype "bidirectional"))
    )
    (net (code "69") (name "PWREN#") (class "Default")
      (node (ref "IC1") (pin "13") (pinfunction "G_13") (pintype "input"))
      (node (ref "R26") (pin "2") (pinfunction "2_2") (pintype "passive"))
      (node (ref "U1") (pin "60") (pinfunction "PWREN#_60") (pintype "bidirectional"))
    )
    (net (code "70") (name "RI#_A") (class "Default")
      (node (ref "U1") (pin "24") (pinfunction "ADBUS7_24") (pintype "bidirectional"))
    )
    (net (code "71") (name "RI#_B") (class "Default")
      (node (ref "U1") (pin "34") (pinfunction "BDBUS7_34") (pintype "bidirectional"))
    )
    (net (code "72") (name "RI#_C") (class "Default")
      (node (ref "U1") (pin "46") (pinfunction "CDBUS7_46") (pintype "bidirectional"))
    )
    (net (code "73") (name "RI#_D") (class "Default")
      (node (ref "U1") (pin "59") (pinfunction "DDBUS7_59") (pintype "bidirectional"))
    )
    (net (code "74") (name "RTS#_A") (class "Default")
      (node (ref "U1") (pin "18") (pinfunction "ADBUS2_18") (pintype "bidirectional"))
    )
    (net (code "75") (name "RTS#_B") (class "Default")
      (node (ref "U1") (pin "28") (pinfunction "BDBUS2_28") (pintype "bidirectional"))
    )
    (net (code "76") (name "RTS#_C") (class "Default")
      (node (ref "U1") (pin "40") (pinfunction "CDBUS2_40") (pintype "bidirectional"))
    )
    (net (code "77") (name "RTS#_D") (class "Default")
      (node (ref "U1") (pin "53") (pinfunction "DDBUS2_53") (pintype "bidirectional"))
    )
    (net (code "78") (name "RXD_A") (class "Default")
      (node (ref "FRX_A") (pin "1") (pinfunction "VO_1") (pintype "passive"))
      (node (ref "FRX_A") (pin "4") (pinfunction "RL_4") (pintype "passive"))
      (node (ref "U1") (pin "17") (pinfunction "ADBUS1_17") (pintype "bidirectional"))
    )
    (net (code "79") (name "RXD_B") (class "Default")
      (node (ref "FRX_B") (pin "1") (pinfunction "VO_1") (pintype "passive"))
      (node (ref "FRX_B") (pin "4") (pinfunction "RL_4") (pintype "passive"))
      (node (ref "U1") (pin "27") (pinfunction "BDBUS1_27") (pintype "bidirectional"))
    )
    (net (code "80") (name "RXD_C") (class "Default")
      (node (ref "FRX_C") (pin "1") (pinfunction "VO_1") (pintype "passive"))
      (node (ref "FRX_C") (pin "4") (pinfunction "RL_4") (pintype "passive"))
      (node (ref "U1") (pin "39") (pinfunction "CDBUS1_39") (pintype "bidirectional"))
    )
    (net (code "81") (name "RXD_D") (class "Default")
      (node (ref "FRX_D") (pin "1") (pinfunction "VO_1") (pintype "passive"))
      (node (ref "FRX_D") (pin "4") (pinfunction "RL_4") (pintype "passive"))
      (node (ref "U1") (pin "52") (pinfunction "DDBUS1_52") (pintype "bidirectional"))
    )
    (net (code "82") (name "TXD_A") (class "Default")
      (node (ref "R27") (pin "1") (pinfunction "1_1") (pintype "passive"))
      (node (ref "U1") (pin "16") (pinfunction "ADBUS0_16") (pintype "bidirectional"))
    )
    (net (code "83") (name "TXD_B") (class "Default")
      (node (ref "R6") (pin "1") (pinfunction "1_1") (pintype "passive"))
      (node (ref "U1") (pin "26") (pinfunction "BDBUS0_26") (pintype "bidirectional"))
    )
    (net (code "84") (name "TXD_C") (class "Default")
      (node (ref "R8") (pin "1") (pinfunction "1_1") (pintype "passive"))
      (node (ref "U1") (pin "38") (pinfunction "CDBUS0_38") (pintype "bidirectional"))
    )
    (net (code "85") (name "TXD_D") (class "Default")
      (node (ref "R10") (pin "1") (pinfunction "1_1") (pintype "passive"))
      (node (ref "U1") (pin "48") (pinfunction "DDBUS0_48") (pintype "bidirectional"))
    )
    (net (code "86") (name "VUSB") (class "Default")
      (node (ref "C19") (pin "1") (pinfunction "1_1") (pintype "passive"))
      (node (ref "C2") (pin "1") (pinfunction "1_1") (pintype "passive"))
      (node (ref "C20") (pin "1") (pinfunction "1_1") (pintype "passive"))
      (node (ref "C22") (pin "1") (pinfunction "1_1") (pintype "passive"))
      (node (ref "C23") (pin "1") (pinfunction "1_1") (pintype "passive"))
      (node (ref "C25") (pin "1") (pinfunction "1_1") (pintype "passive"))
      (node (ref "C26") (pin "1") (pinfunction "1_1") (pintype "passive"))
      (node (ref "C28") (pin "1") (pinfunction "1_1") (pintype "passive"))
      (node (ref "C29") (pin "1") (pinfunction "1_1") (pintype "passive"))
      (node (ref "R19") (pin "1") (pinfunction "1_1") (pintype "passive"))
      (node (ref "R28") (pin "1") (pinfunction "1_1") (pintype "passive"))
      (node (ref "R5") (pin "1") (pinfunction "1_1") (pintype "passive"))
      (node (ref "R7") (pin "1") (pinfunction "1_1") (pintype "passive"))
      (node (ref "R9") (pin "1") (pinfunction "1_1") (pintype "passive"))
      (node (ref "USB_TYPEB_FEMALE") (pin "1") (pinfunction "1_1") (pintype "passive"))
      (node (ref "VREG1") (pin "3") (pinfunction "VIN_3") (pintype "bidirectional"))
    )
    (net (code "87") (name "unconnected-(IC1A-QH*-Pad9)") (class "Default")
      (node (ref "IC1") (pin "9") (pinfunction "QH*_9") (pintype "tri_state"))
    )
    (net (code "88") (name "unconnected-(U1-SUSPEND#-Pad36)") (class "Default")
      (node (ref "U1") (pin "36") (pinfunction "SUSPEND#_36") (pintype "bidirectional"))
    )
  )
)
